# SCH_VisionInspect-S3_2026-02-28.net
KiCad netlist of a schematic drawn in EasyEDA
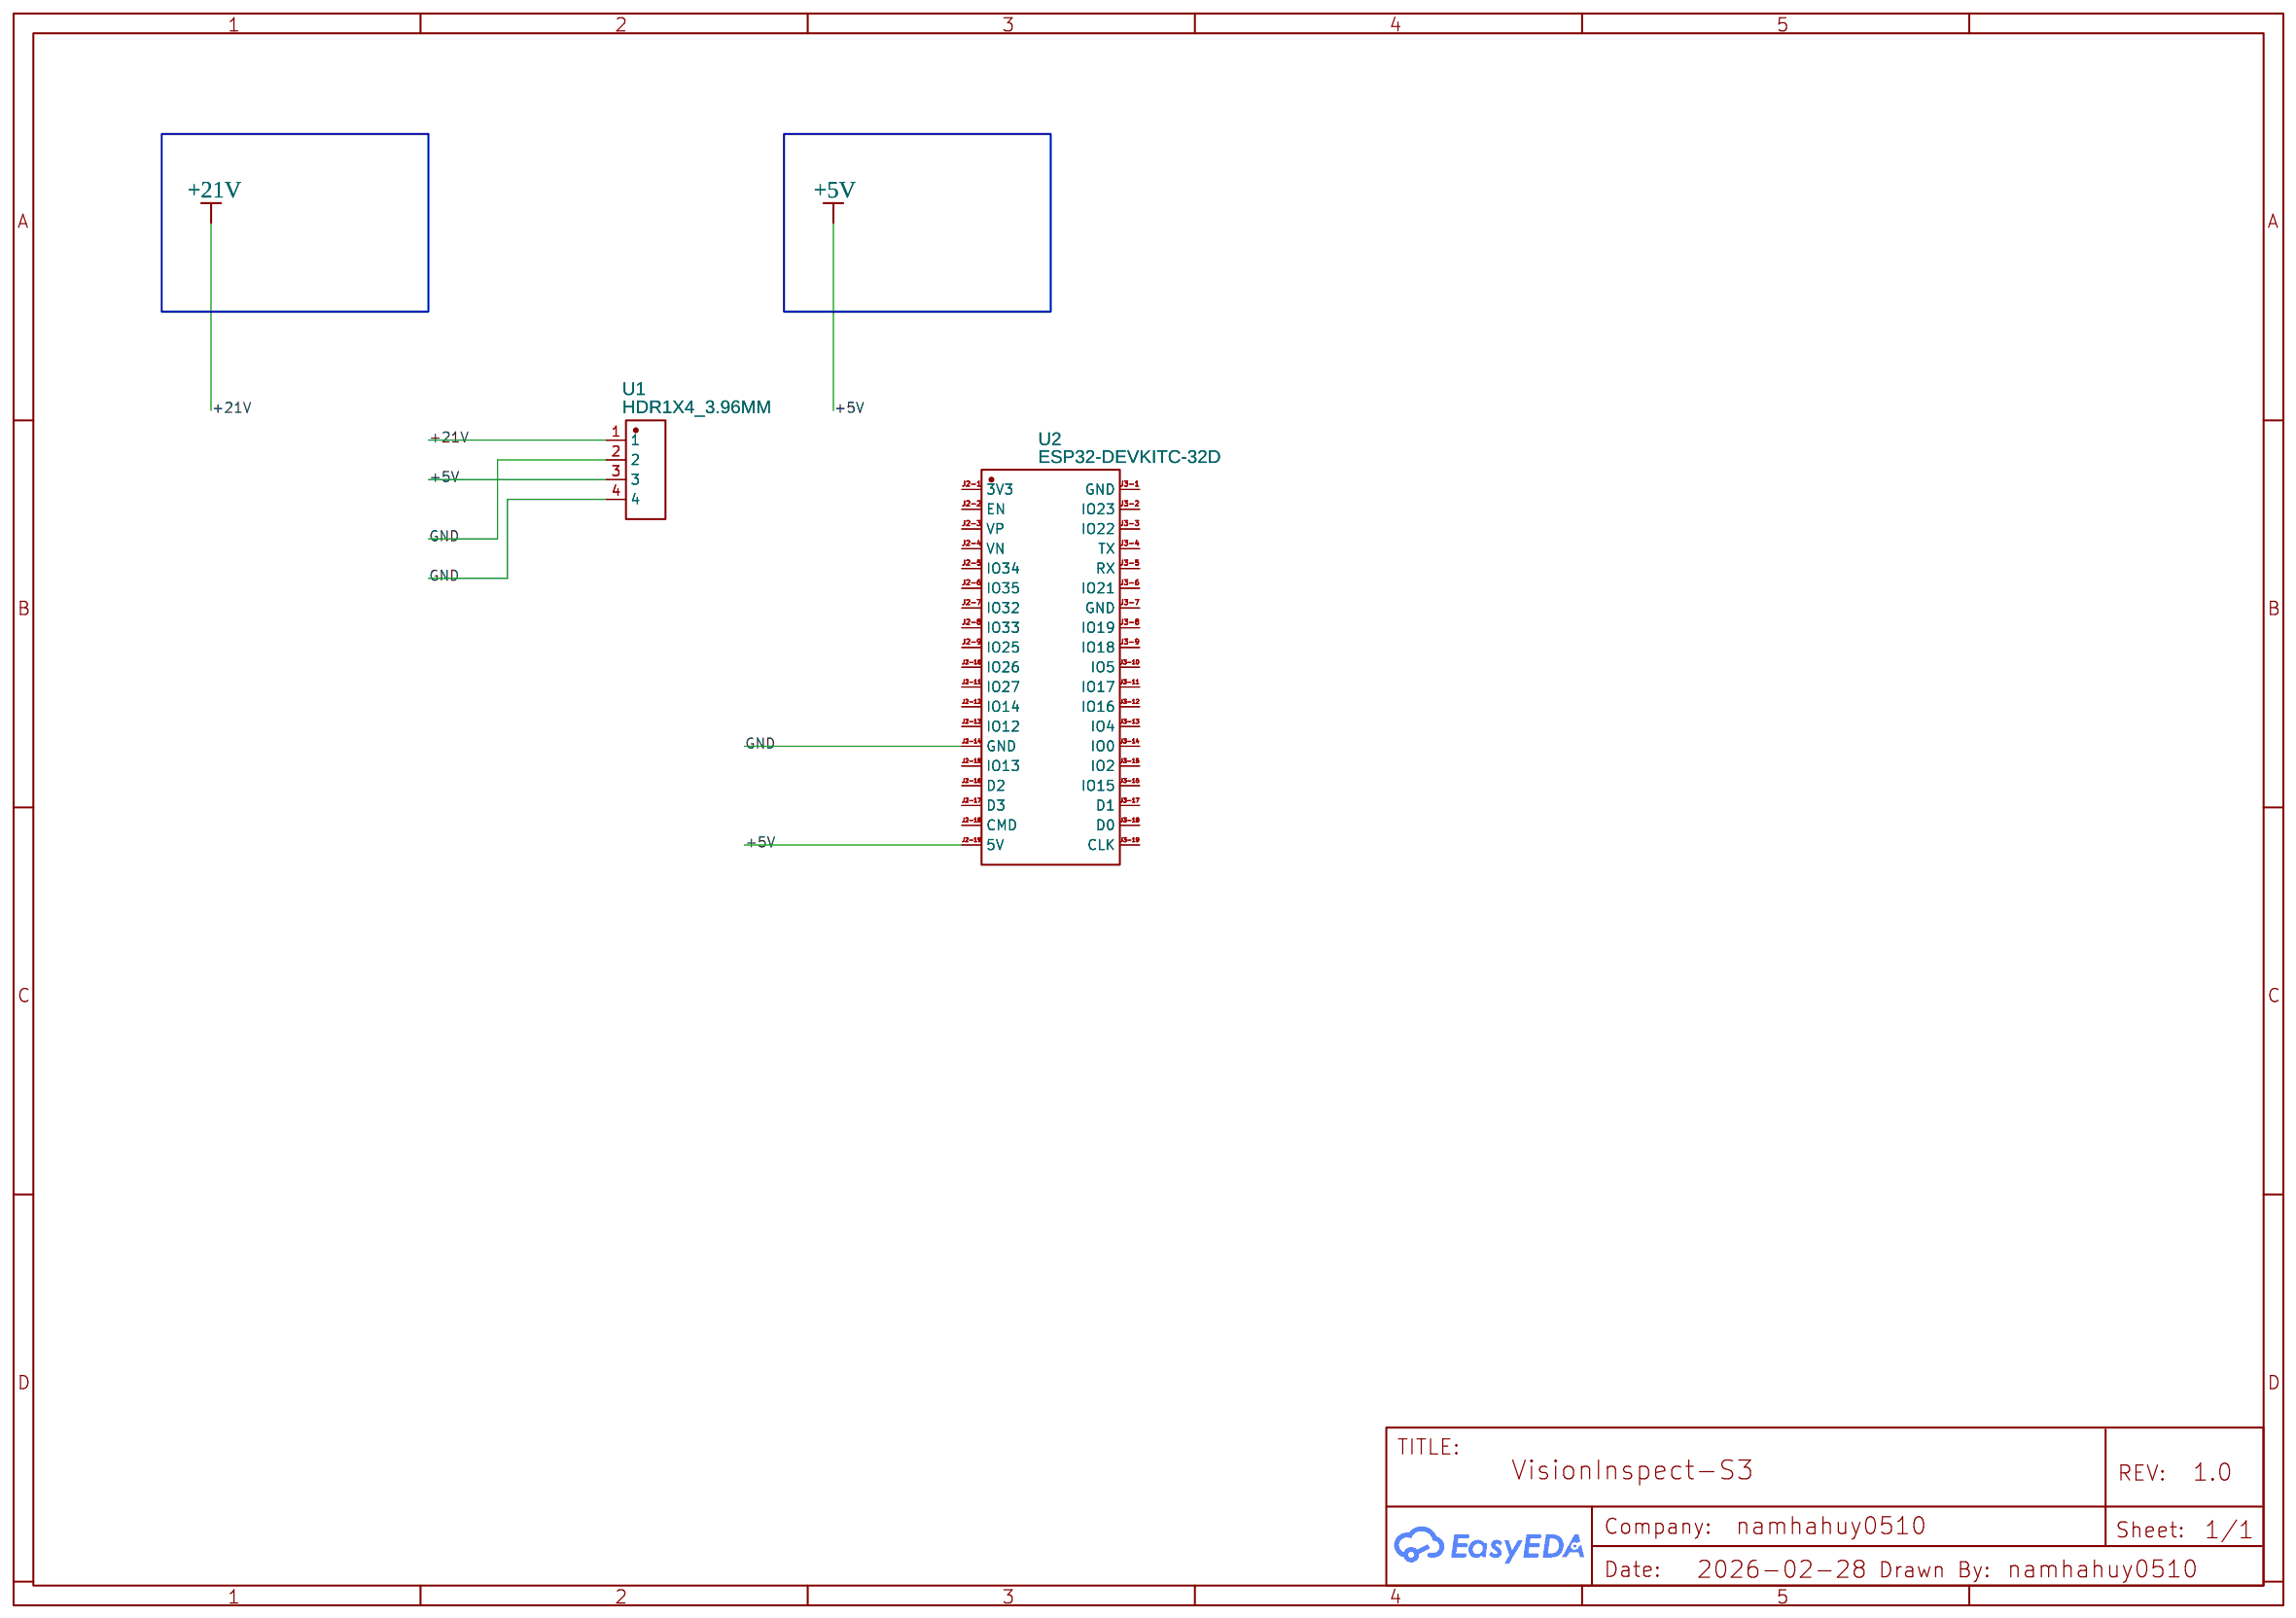
[diagram p0: schematic sheet]

(export (version "E")
  (design (tool "Eeschema 10.0.6"))
  (components
    (comp (ref "U1")
      (value "HDR1X4_3.96MM")
      (fields (field (name "Manufacturer Part") "HDR1X4_3.96mm"))
      (libsource (lib "") (part "HDR1X4_3.96MM"))
    )
    (comp (ref "U2")
      (value "ESP32-DEVKITC-32D")
      (fields
        (field (name "Manufacturer Part") "ESP32-DevKitC-32D")
        (field (name "Manufacturer") "ESPRESSIF(乐鑫)")
      )
      (libsource (lib "") (part "ESP32-DEVKITC-32D"))
    )
  )
  (nets
    (net (code "1") (name "+5V") (class "Default")
      (node (ref "U1") (pin "3") (pinfunction "3_3") (pintype "unspecified"))
      (node (ref "U2") (pin "J2-19") (pinfunction "5V_J2-19") (pintype "unspecified"))
    )
    (net (code "2") (name "+21V") (class "Default")
      (node (ref "U1") (pin "1") (pinfunction "1_1") (pintype "unspecified"))
    )
    (net (code "3") (name "/GND") (class "Default")
      (node (ref "U1") (pin "2") (pinfunction "2_2") (pintype "unspecified"))
      (node (ref "U1") (pin "4") (pinfunction "4_4") (pintype "unspecified"))
      (node (ref "U2") (pin "J2-14") (pinfunction "GND_J2-14") (pintype "unspecified"))
    )
    (net (code "4") (name "unconnected-(U2-3V3-PadJ2-1)") (class "Default")
      (node (ref "U2") (pin "J2-1") (pinfunction "3V3_J2-1") (pintype "unspecified"))
    )
    (net (code "5") (name "unconnected-(U2-CLK-PadJ3-19)") (class "Default")
      (node (ref "U2") (pin "J3-19") (pinfunction "CLK_J3-19") (pintype "unspecified"))
    )
    (net (code "6") (name "unconnected-(U2-CMD-PadJ2-18)") (class "Default")
      (node (ref "U2") (pin "J2-18") (pinfunction "CMD_J2-18") (pintype "unspecified"))
    )
    (net (code "7") (name "unconnected-(U2-D0-PadJ3-18)") (class "Default")
      (node (ref "U2") (pin "J3-18") (pinfunction "D0_J3-18") (pintype "unspecified"))
    )
    (net (code "8") (name "unconnected-(U2-D1-PadJ3-17)") (class "Default")
      (node (ref "U2") (pin "J3-17") (pinfunction "D1_J3-17") (pintype "unspecified"))
    )
    (net (code "9") (name "unconnected-(U2-D2-PadJ2-16)") (class "Default")
      (node (ref "U2") (pin "J2-16") (pinfunction "D2_J2-16") (pintype "unspecified"))
    )
    (net (code "10") (name "unconnected-(U2-D3-PadJ2-17)") (class "Default")
      (node (ref "U2") (pin "J2-17") (pinfunction "D3_J2-17") (pintype "unspecified"))
    )
    (net (code "11") (name "unconnected-(U2-EN-PadJ2-2)") (class "Default")
      (node (ref "U2") (pin "J2-2") (pinfunction "EN_J2-2") (pintype "unspecified"))
    )
    (net (code "12") (name "unconnected-(U2-GND-PadJ3-1)") (class "Default")
      (node (ref "U2") (pin "J3-1") (pinfunction "GND_J3-1") (pintype "unspecified"))
    )
    (net (code "13") (name "unconnected-(U2-GND-PadJ3-7)") (class "Default")
      (node (ref "U2") (pin "J3-7") (pinfunction "GND_J3-7") (pintype "unspecified"))
    )
    (net (code "14") (name "unconnected-(U2-IO0-PadJ3-14)") (class "Default")
      (node (ref "U2") (pin "J3-14") (pinfunction "IO0_J3-14") (pintype "unspecified"))
    )
    (net (code "15") (name "unconnected-(U2-IO2-PadJ3-15)") (class "Default")
      (node (ref "U2") (pin "J3-15") (pinfunction "IO2_J3-15") (pintype "unspecified"))
    )
    (net (code "16") (name "unconnected-(U2-IO4-PadJ3-13)") (class "Default")
      (node (ref "U2") (pin "J3-13") (pinfunction "IO4_J3-13") (pintype "unspecified"))
    )
    (net (code "17") (name "unconnected-(U2-IO5-PadJ3-10)") (class "Default")
      (node (ref "U2") (pin "J3-10") (pinfunction "IO5_J3-10") (pintype "unspecified"))
    )
    (net (code "18") (name "unconnected-(U2-IO12-PadJ2-13)") (class "Default")
      (node (ref "U2") (pin "J2-13") (pinfunction "IO12_J2-13") (pintype "unspecified"))
    )
    (net (code "19") (name "unconnected-(U2-IO13-PadJ2-15)") (class "Default")
      (node (ref "U2") (pin "J2-15") (pinfunction "IO13_J2-15") (pintype "unspecified"))
    )
    (net (code "20") (name "unconnected-(U2-IO14-PadJ2-12)") (class "Default")
      (node (ref "U2") (pin "J2-12") (pinfunction "IO14_J2-12") (pintype "unspecified"))
    )
    (net (code "21") (name "unconnected-(U2-IO15-PadJ3-16)") (class "Default")
      (node (ref "U2") (pin "J3-16") (pinfunction "IO15_J3-16") (pintype "unspecified"))
    )
    (net (code "22") (name "unconnected-(U2-IO16-PadJ3-12)") (class "Default")
      (node (ref "U2") (pin "J3-12") (pinfunction "IO16_J3-12") (pintype "unspecified"))
    )
    (net (code "23") (name "unconnected-(U2-IO17-PadJ3-11)") (class "Default")
      (node (ref "U2") (pin "J3-11") (pinfunction "IO17_J3-11") (pintype "unspecified"))
    )
    (net (code "24") (name "unconnected-(U2-IO18-PadJ3-9)") (class "Default")
      (node (ref "U2") (pin "J3-9") (pinfunction "IO18_J3-9") (pintype "unspecified"))
    )
    (net (code "25") (name "unconnected-(U2-IO19-PadJ3-8)") (class "Default")
      (node (ref "U2") (pin "J3-8") (pinfunction "IO19_J3-8") (pintype "unspecified"))
    )
    (net (code "26") (name "unconnected-(U2-IO21-PadJ3-6)") (class "Default")
      (node (ref "U2") (pin "J3-6") (pinfunction "IO21_J3-6") (pintype "unspecified"))
    )
    (net (code "27") (name "unconnected-(U2-IO22-PadJ3-3)") (class "Default")
      (node (ref "U2") (pin "J3-3") (pinfunction "IO22_J3-3") (pintype "unspecified"))
    )
    (net (code "28") (name "unconnected-(U2-IO23-PadJ3-2)") (class "Default")
      (node (ref "U2") (pin "J3-2") (pinfunction "IO23_J3-2") (pintype "unspecified"))
    )
    (net (code "29") (name "unconnected-(U2-IO25-PadJ2-9)") (class "Default")
      (node (ref "U2") (pin "J2-9") (pinfunction "IO25_J2-9") (pintype "unspecified"))
    )
    (net (code "30") (name "unconnected-(U2-IO26-PadJ2-10)") (class "Default")
      (node (ref "U2") (pin "J2-10") (pinfunction "IO26_J2-10") (pintype "unspecified"))
    )
    (net (code "31") (name "unconnected-(U2-IO27-PadJ2-11)") (class "Default")
      (node (ref "U2") (pin "J2-11") (pinfunction "IO27_J2-11") (pintype "unspecified"))
    )
    (net (code "32") (name "unconnected-(U2-IO32-PadJ2-7)") (class "Default")
      (node (ref "U2") (pin "J2-7") (pinfunction "IO32_J2-7") (pintype "unspecified"))
    )
    (net (code "33") (name "unconnected-(U2-IO33-PadJ2-8)") (class "Default")
      (node (ref "U2") (pin "J2-8") (pinfunction "IO33_J2-8") (pintype "unspecified"))
    )
    (net (code "34") (name "unconnected-(U2-IO34-PadJ2-5)") (class "Default")
      (node (ref "U2") (pin "J2-5") (pinfunction "IO34_J2-5") (pintype "unspecified"))
    )
    (net (code "35") (name "unconnected-(U2-IO35-PadJ2-6)") (class "Default")
      (node (ref "U2") (pin "J2-6") (pinfunction "IO35_J2-6") (pintype "unspecified"))
    )
    (net (code "36") (name "unconnected-(U2-RX-PadJ3-5)") (class "Default")
      (node (ref "U2") (pin "J3-5") (pinfunction "RX_J3-5") (pintype "unspecified"))
    )
    (net (code "37") (name "unconnected-(U2-TX-PadJ3-4)") (class "Default")
      (node (ref "U2") (pin "J3-4") (pinfunction "TX_J3-4") (pintype "unspecified"))
    )
    (net (code "38") (name "unconnected-(U2-VN-PadJ2-4)") (class "Default")
      (node (ref "U2") (pin "J2-4") (pinfunction "VN_J2-4") (pintype "unspecified"))
    )
    (net (code "39") (name "unconnected-(U2-VP-PadJ2-3)") (class "Default")
      (node (ref "U2") (pin "J2-3") (pinfunction "VP_J2-3") (pintype "unspecified"))
    )
  )
)
